# Sch_v1.net
KiCad netlist of a schematic drawn in Altium Designer
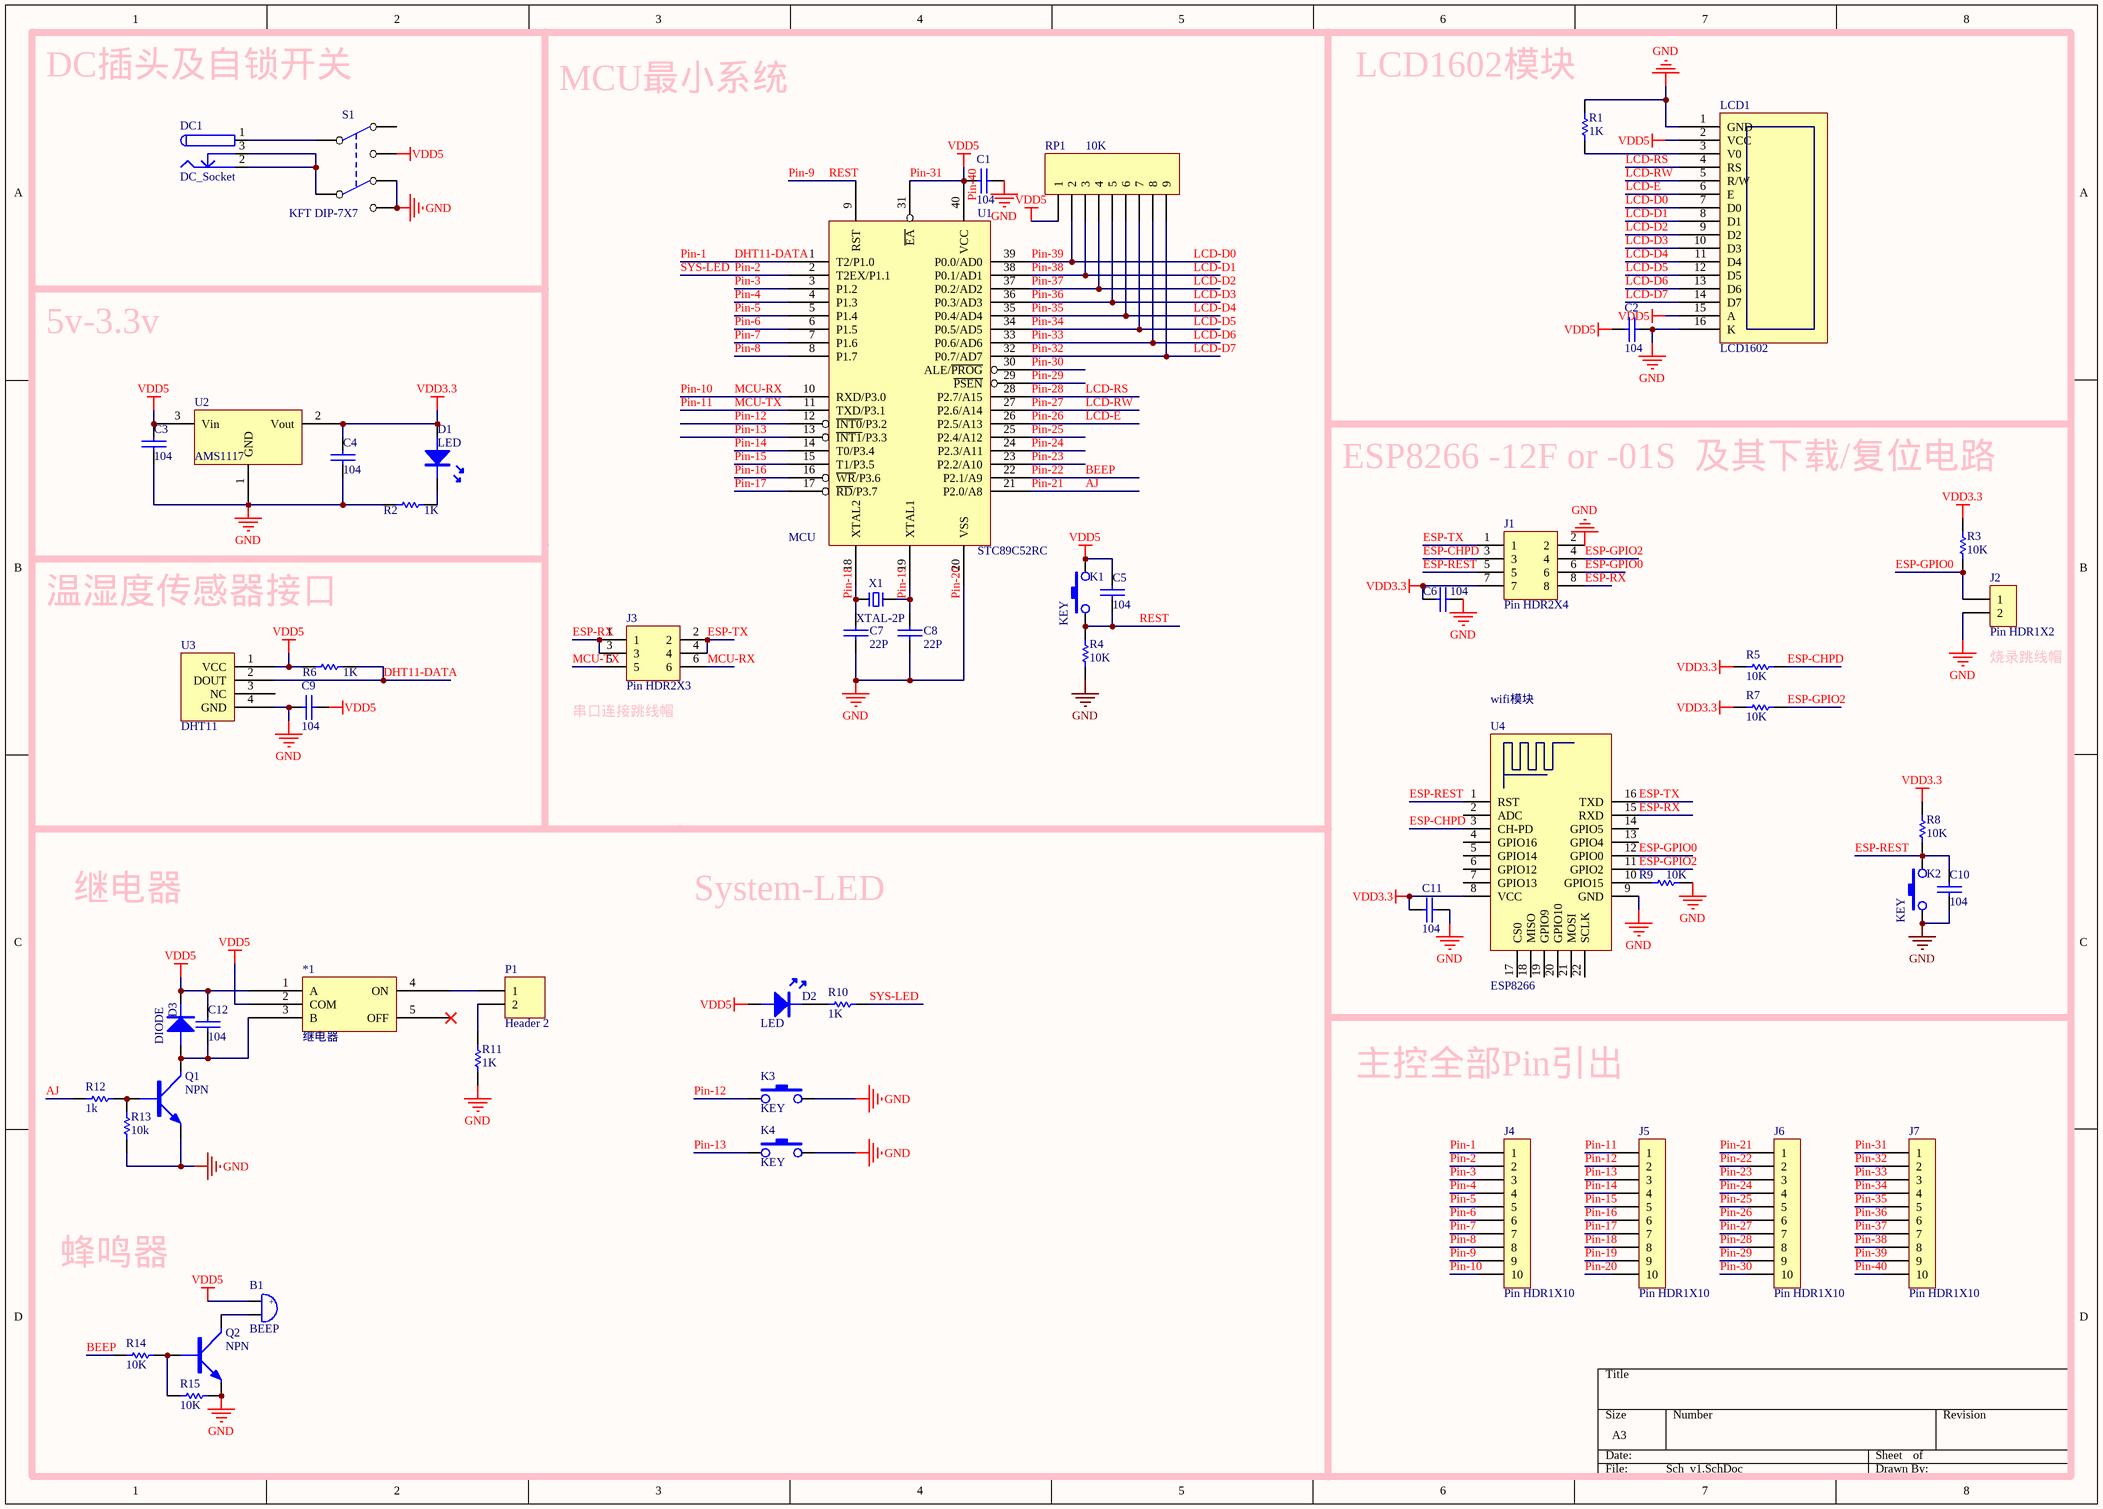
[diagram p0: Sch_v1.SchDoc]

(export (version "E")
  (design (tool "Eeschema 10.0.6"))
  (components
    (comp (ref "*1") (value "继电器") (footprint "继电器") (libsource (lib "test") (part "继电器")))
    (comp (ref "B1")
      (value "BEEP")
      (footprint "BEEP 6.5x12x8.5")
      (description "蜂鸣器")
      (libsource (lib "蜂鸣器") (part "BEEP"))
    )
    (comp (ref "C1")
      (value "104")
      (footprint "0805C")
      (description "无极性电容")
      (libsource (lib "电容") (part "CAP"))
    )
    (comp (ref "C2")
      (value "104")
      (footprint "0805C")
      (description "无极性电容")
      (libsource (lib "电容") (part "CAP"))
    )
    (comp (ref "C3")
      (value "104")
      (footprint "0805C")
      (description "无极性电容")
      (libsource (lib "电容") (part "CAP"))
    )
    (comp (ref "C4")
      (value "104")
      (footprint "0805C")
      (description "无极性电容")
      (libsource (lib "电容") (part "CAP"))
    )
    (comp (ref "C5")
      (value "104")
      (footprint "0805C")
      (description "无极性电容")
      (libsource (lib "电容") (part "CAP"))
    )
    (comp (ref "C6")
      (value "104")
      (footprint "0805C")
      (description "无极性电容")
      (libsource (lib "电容") (part "CAP"))
    )
    (comp (ref "C7")
      (value "22P")
      (footprint "0805C")
      (description "无极性电容")
      (libsource (lib "电容") (part "CAP"))
    )
    (comp (ref "C8")
      (value "22P")
      (footprint "0805C")
      (description "无极性电容")
      (libsource (lib "电容") (part "CAP"))
    )
    (comp (ref "C9")
      (value "104")
      (footprint "0805C")
      (description "无极性电容")
      (libsource (lib "电容") (part "CAP"))
    )
    (comp (ref "C10")
      (value "104")
      (footprint "0805C")
      (description "无极性电容")
      (libsource (lib "电容") (part "CAP"))
    )
    (comp (ref "C11")
      (value "104")
      (footprint "0805C")
      (description "无极性电容")
      (libsource (lib "电容") (part "CAP"))
    )
    (comp (ref "C12")
      (value "104")
      (footprint "0805C")
      (description "无极性电容")
      (libsource (lib "电容") (part "CAP"))
    )
    (comp (ref "D1") (value "LED") (footprint "LED-0805R") (libsource (lib "LED") (part "LED")))
    (comp (ref "D2") (value "LED") (footprint "LED-0805R") (libsource (lib "LED") (part "LED")))
    (comp (ref "D3")
      (value "DIODE")
      (footprint "LL34")
      (description "普通二极管")
      (libsource (lib "二极管") (part "DIODE"))
    )
    (comp (ref "DC1") (value "DC_Socket") (footprint "DC-005") (libsource (lib "电源插座") (part "DC_Socket")))
    (comp (ref "J1")
      (value "Pin HDR2X4")
      (footprint "Pin HDR2X4/2.54mm-S")
      (libsource (lib "排针") (part "Pin HDR2X4"))
    )
    (comp (ref "J2")
      (value "Pin HDR1X2")
      (footprint "Pin HDR1X2/2.54mm-S")
      (libsource (lib "排针") (part "Pin HDR1X2"))
    )
    (comp (ref "J3")
      (value "Pin HDR2X3")
      (footprint "Pin HDR2X3/2.54mm-S")
      (libsource (lib "排针") (part "Pin HDR2X3"))
    )
    (comp (ref "J4")
      (value "Pin HDR1X10")
      (footprint "Pin HDR1X10/2.54mm-S")
      (libsource (lib "排针") (part "Pin HDR1X10"))
    )
    (comp (ref "J5")
      (value "Pin HDR1X10")
      (footprint "Pin HDR1X10/2.54mm-S")
      (libsource (lib "排针") (part "Pin HDR1X10"))
    )
    (comp (ref "J6")
      (value "Pin HDR1X10")
      (footprint "Pin HDR1X10/2.54mm-S")
      (libsource (lib "排针") (part "Pin HDR1X10"))
    )
    (comp (ref "J7")
      (value "Pin HDR1X10")
      (footprint "Pin HDR1X10/2.54mm-S")
      (libsource (lib "排针") (part "Pin HDR1X10"))
    )
    (comp (ref "K1") (value "KEY") (footprint "SMD-3X6X2.5") (libsource (lib "轻触开关") (part "KEY")))
    (comp (ref "K2") (value "KEY") (footprint "SMD-3X6X2.5") (libsource (lib "轻触开关") (part "KEY")))
    (comp (ref "K3") (value "KEY") (footprint "SMD-3X6X2.5") (libsource (lib "轻触开关") (part "KEY")))
    (comp (ref "K4") (value "KEY") (footprint "SMD-3X6X2.5") (libsource (lib "轻触开关") (part "KEY")))
    (comp (ref "LCD1")
      (value "LCD1602")
      (footprint "Fe-HDR1X16/2.54-S")
      (libsource (lib "SS") (part "LCD1602"))
    )
    (comp (ref "P1")
      (value "Header 2")
      (footprint "HDR1X2")
      (description "Header, 2-Pin")
      (fields (field (name "PUBLISHER") "Altium Limited"))
      (libsource (lib "Miscellaneous Connectors") (part "Header 2"))
    )
    (comp (ref "Q1")
      (value "NPN")
      (footprint "SOT-23")
      (description "NPN三极管")
      (libsource (lib "三极管") (part "NPN"))
    )
    (comp (ref "Q2")
      (value "NPN")
      (footprint "SOT-23")
      (description "NPN三极管")
      (libsource (lib "三极管") (part "NPN"))
    )
    (comp (ref "R1") (value "1K") (footprint "0805R") (libsource (lib "电阻") (part "RES")))
    (comp (ref "R2") (value "1K") (footprint "0805R") (libsource (lib "电阻") (part "RES")))
    (comp (ref "R3") (value "10K") (footprint "0805R") (libsource (lib "电阻") (part "RES")))
    (comp (ref "R4") (value "10K") (footprint "0805R") (libsource (lib "电阻") (part "RES")))
    (comp (ref "R5") (value "10K") (footprint "0805R") (libsource (lib "电阻") (part "RES")))
    (comp (ref "R6") (value "1K") (footprint "0805R") (libsource (lib "电阻") (part "RES")))
    (comp (ref "R7") (value "10K") (footprint "0805R") (libsource (lib "电阻") (part "RES")))
    (comp (ref "R8") (value "10K") (footprint "0805R") (libsource (lib "电阻") (part "RES")))
    (comp (ref "R9") (value "10K") (footprint "0805R") (libsource (lib "电阻") (part "RES")))
    (comp (ref "R10") (value "1K") (footprint "0805R") (libsource (lib "电阻") (part "RES")))
    (comp (ref "R11") (value "1K") (footprint "0805R") (libsource (lib "电阻") (part "RES")))
    (comp (ref "R12") (value "1k") (footprint "0805R") (libsource (lib "电阻") (part "RES")))
    (comp (ref "R13") (value "10k") (footprint "0805R") (libsource (lib "电阻") (part "RES")))
    (comp (ref "R14") (value "10K") (footprint "0805R") (libsource (lib "电阻") (part "RES")))
    (comp (ref "R15") (value "10K") (footprint "0805R") (libsource (lib "电阻") (part "RES")))
    (comp (ref "RP1")
      (value "10K")
      (footprint "HDR1X9")
      (description "Header, 9-Pin")
      (fields (field (name "PUBLISHER") "Altium Limited"))
      (libsource (lib "Miscellaneous Connectors") (part "Header 9"))
    )
    (comp (ref "S1")
      (value "KFT DIP-7X7")
      (footprint "KFT DIP-8X8")
      (libsource (lib "电源开关") (part "KFT DIP-7X7"))
    )
    (comp (ref "U1") (value "STC89C52RC") (footprint "DIP40") (libsource (lib "SS") (part "STC89C52RC")))
    (comp (ref "U2")
      (value "AMS1117")
      (footprint "SOT223")
      (description "三端稳压芯片")
      (libsource (lib "电源芯片") (part "AMS1117"))
    )
    (comp (ref "U3") (value "DHT11") (footprint "Fe-HDR1X4/2.54-S") (libsource (lib "SS") (part "DHT11")))
    (comp (ref "U4")
      (value "ESP8266")
      (footprint "WIFIM-SMD_ESP-12F-ESP8266MOD")
      (libsource (lib "Sch_v1") (part "ESP8266"))
    )
    (comp (ref "X1")
      (value "XTAL-2P")
      (footprint "OSC HC-49S")
      (description "2脚无源脚晶振")
      (libsource (lib "晶振") (part "XTAL-2P"))
    )
  )
  (nets
    (net (code "1") (name "/AJ") (class "Default")
      (node (ref "J6") (pin "1") (pinfunction "1_1") (pintype "passive"))
      (node (ref "R12") (pin "2") (pinfunction "2_2") (pintype "passive"))
      (node (ref "U1") (pin "21") (pinfunction "P2.0/A8_21") (pintype "passive"))
    )
    (net (code "2") (name "/BEEP") (class "Default")
      (node (ref "J6") (pin "2") (pinfunction "2_2") (pintype "passive"))
      (node (ref "R14") (pin "2") (pinfunction "2_2") (pintype "passive"))
      (node (ref "U1") (pin "22") (pinfunction "P2.1/A9_22") (pintype "passive"))
    )
    (net (code "3") (name "/DHT11-DATA") (class "Default")
      (node (ref "J4") (pin "1") (pinfunction "1_1") (pintype "passive"))
      (node (ref "R6") (pin "1") (pinfunction "1_1") (pintype "passive"))
      (node (ref "U1") (pin "1") (pinfunction "T2/P1.0_1") (pintype "passive"))
      (node (ref "U3") (pin "2") (pinfunction "DOUT_2") (pintype "passive"))
    )
    (net (code "4") (name "/ESP-CHPD") (class "Default")
      (node (ref "J1") (pin "3") (pinfunction "3_3") (pintype "passive"))
      (node (ref "R5") (pin "2") (pinfunction "2_2") (pintype "passive"))
      (node (ref "U4") (pin "3") (pinfunction "CH-PD_3") (pintype "passive"))
    )
    (net (code "5") (name "/ESP-GPIO0") (class "Default")
      (node (ref "J1") (pin "6") (pinfunction "6_6") (pintype "passive"))
      (node (ref "J2") (pin "1") (pinfunction "1_1") (pintype "passive"))
      (node (ref "R3") (pin "1") (pinfunction "1_1") (pintype "passive"))
      (node (ref "U4") (pin "12") (pinfunction "GPIO0_12") (pintype "passive"))
    )
    (net (code "6") (name "/ESP-GPIO2") (class "Default")
      (node (ref "J1") (pin "4") (pinfunction "4_4") (pintype "passive"))
      (node (ref "R7") (pin "2") (pinfunction "2_2") (pintype "passive"))
      (node (ref "U4") (pin "11") (pinfunction "GPIO2_11") (pintype "passive"))
    )
    (net (code "7") (name "/ESP-REST") (class "Default")
      (node (ref "C10") (pin "2") (pinfunction "2_2") (pintype "passive"))
      (node (ref "J1") (pin "5") (pinfunction "5_5") (pintype "passive"))
      (node (ref "K2") (pin "3") (pinfunction "3_3") (pintype "passive"))
      (node (ref "R8") (pin "1") (pinfunction "1_1") (pintype "passive"))
      (node (ref "U4") (pin "1") (pinfunction "RST_1") (pintype "open_emitter"))
    )
    (net (code "8") (name "/ESP-RX") (class "Default")
      (node (ref "J1") (pin "8") (pinfunction "8_8") (pintype "passive"))
      (node (ref "J3") (pin "1") (pinfunction "1_1") (pintype "passive"))
      (node (ref "J3") (pin "3") (pinfunction "3_3") (pintype "passive"))
      (node (ref "U4") (pin "15") (pinfunction "RXD_15") (pintype "passive"))
    )
    (net (code "9") (name "/ESP-TX") (class "Default")
      (node (ref "J1") (pin "1") (pinfunction "1_1") (pintype "passive"))
      (node (ref "J3") (pin "2") (pinfunction "2_2") (pintype "passive"))
      (node (ref "J3") (pin "4") (pinfunction "4_4") (pintype "passive"))
      (node (ref "U4") (pin "16") (pinfunction "TXD_16") (pintype "passive"))
    )
    (net (code "10") (name "/LCD-D0") (class "Default")
      (node (ref "J7") (pin "9") (pinfunction "9_9") (pintype "passive"))
      (node (ref "LCD1") (pin "7") (pinfunction "D0_7") (pintype "passive"))
      (node (ref "RP1") (pin "2") (pinfunction "2_2") (pintype "passive"))
      (node (ref "U1") (pin "39") (pinfunction "P0.0/AD0_39") (pintype "passive"))
    )
    (net (code "11") (name "/LCD-D1") (class "Default")
      (node (ref "J7") (pin "8") (pinfunction "8_8") (pintype "passive"))
      (node (ref "LCD1") (pin "8") (pinfunction "D1_8") (pintype "passive"))
      (node (ref "RP1") (pin "3") (pinfunction "3_3") (pintype "passive"))
      (node (ref "U1") (pin "38") (pinfunction "P0.1/AD1_38") (pintype "passive"))
    )
    (net (code "12") (name "/LCD-D2") (class "Default")
      (node (ref "J7") (pin "7") (pinfunction "7_7") (pintype "passive"))
      (node (ref "LCD1") (pin "9") (pinfunction "D2_9") (pintype "passive"))
      (node (ref "RP1") (pin "4") (pinfunction "4_4") (pintype "passive"))
      (node (ref "U1") (pin "37") (pinfunction "P0.2/AD2_37") (pintype "passive"))
    )
    (net (code "13") (name "/LCD-D3") (class "Default")
      (node (ref "J7") (pin "6") (pinfunction "6_6") (pintype "passive"))
      (node (ref "LCD1") (pin "10") (pinfunction "D3_10") (pintype "passive"))
      (node (ref "RP1") (pin "5") (pinfunction "5_5") (pintype "passive"))
      (node (ref "U1") (pin "36") (pinfunction "P0.3/AD3_36") (pintype "passive"))
    )
    (net (code "14") (name "/LCD-D4") (class "Default")
      (node (ref "J7") (pin "5") (pinfunction "5_5") (pintype "passive"))
      (node (ref "LCD1") (pin "11") (pinfunction "D4_11") (pintype "passive"))
      (node (ref "RP1") (pin "6") (pinfunction "6_6") (pintype "passive"))
      (node (ref "U1") (pin "35") (pinfunction "P0.4/AD4_35") (pintype "passive"))
    )
    (net (code "15") (name "/LCD-D5") (class "Default")
      (node (ref "J7") (pin "4") (pinfunction "4_4") (pintype "passive"))
      (node (ref "LCD1") (pin "12") (pinfunction "D5_12") (pintype "passive"))
      (node (ref "RP1") (pin "7") (pinfunction "7_7") (pintype "passive"))
      (node (ref "U1") (pin "34") (pinfunction "P0.5/AD5_34") (pintype "passive"))
    )
    (net (code "16") (name "/LCD-D6") (class "Default")
      (node (ref "J7") (pin "3") (pinfunction "3_3") (pintype "passive"))
      (node (ref "LCD1") (pin "13") (pinfunction "D6_13") (pintype "passive"))
      (node (ref "RP1") (pin "8") (pinfunction "8_8") (pintype "passive"))
      (node (ref "U1") (pin "33") (pinfunction "P0.6/AD6_33") (pintype "passive"))
    )
    (net (code "17") (name "/LCD-D7") (class "Default")
      (node (ref "J7") (pin "2") (pinfunction "2_2") (pintype "passive"))
      (node (ref "LCD1") (pin "14") (pinfunction "D7_14") (pintype "passive"))
      (node (ref "RP1") (pin "9") (pinfunction "9_9") (pintype "passive"))
      (node (ref "U1") (pin "32") (pinfunction "P0.7/AD7_32") (pintype "passive"))
    )
    (net (code "18") (name "/LCD-E") (class "Default")
      (node (ref "J6") (pin "6") (pinfunction "6_6") (pintype "passive"))
      (node (ref "LCD1") (pin "6") (pinfunction "E_6") (pintype "passive"))
      (node (ref "U1") (pin "26") (pinfunction "P2.5/A13_26") (pintype "passive"))
    )
    (net (code "19") (name "/LCD-RS") (class "Default")
      (node (ref "J6") (pin "8") (pinfunction "8_8") (pintype "passive"))
      (node (ref "LCD1") (pin "4") (pinfunction "RS_4") (pintype "passive"))
      (node (ref "U1") (pin "28") (pinfunction "P2.7/A15_28") (pintype "passive"))
    )
    (net (code "20") (name "/LCD-RW") (class "Default")
      (node (ref "J6") (pin "7") (pinfunction "7_7") (pintype "passive"))
      (node (ref "LCD1") (pin "5") (pinfunction "R/W_5") (pintype "passive"))
      (node (ref "U1") (pin "27") (pinfunction "P2.6/A14_27") (pintype "passive"))
    )
    (net (code "21") (name "/MCU-RX") (class "Default")
      (node (ref "J3") (pin "6") (pinfunction "6_6") (pintype "passive"))
      (node (ref "J4") (pin "10") (pinfunction "10_10") (pintype "passive"))
      (node (ref "U1") (pin "10") (pinfunction "RXD/P3.0_10") (pintype "passive"))
    )
    (net (code "22") (name "/MCU-TX") (class "Default")
      (node (ref "J3") (pin "5") (pinfunction "5_5") (pintype "passive"))
      (node (ref "J5") (pin "1") (pinfunction "1_1") (pintype "passive"))
      (node (ref "U1") (pin "11") (pinfunction "TXD/P3.1_11") (pintype "passive"))
    )
    (net (code "23") (name "/Pin-2") (class "Default")
      (node (ref "J4") (pin "2") (pinfunction "2_2") (pintype "passive"))
      (node (ref "R10") (pin "2") (pinfunction "2_2") (pintype "passive"))
      (node (ref "U1") (pin "2") (pinfunction "T2EX/P1.1_2") (pintype "passive"))
    )
    (net (code "24") (name "/Pin-3") (class "Default")
      (node (ref "J4") (pin "3") (pinfunction "3_3") (pintype "passive"))
      (node (ref "U1") (pin "3") (pinfunction "P1.2_3") (pintype "passive"))
    )
    (net (code "25") (name "/Pin-4") (class "Default")
      (node (ref "J4") (pin "4") (pinfunction "4_4") (pintype "passive"))
      (node (ref "U1") (pin "4") (pinfunction "P1.3_4") (pintype "passive"))
    )
    (net (code "26") (name "/Pin-5") (class "Default")
      (node (ref "J4") (pin "5") (pinfunction "5_5") (pintype "passive"))
      (node (ref "U1") (pin "5") (pinfunction "P1.4_5") (pintype "passive"))
    )
    (net (code "27") (name "/Pin-6") (class "Default")
      (node (ref "J4") (pin "6") (pinfunction "6_6") (pintype "passive"))
      (node (ref "U1") (pin "6") (pinfunction "P1.5_6") (pintype "passive"))
    )
    (net (code "28") (name "/Pin-7") (class "Default")
      (node (ref "J4") (pin "7") (pinfunction "7_7") (pintype "passive"))
      (node (ref "U1") (pin "7") (pinfunction "P1.6_7") (pintype "passive"))
    )
    (net (code "29") (name "/Pin-8") (class "Default")
      (node (ref "J4") (pin "8") (pinfunction "8_8") (pintype "passive"))
      (node (ref "U1") (pin "8") (pinfunction "P1.7_8") (pintype "passive"))
    )
    (net (code "30") (name "/Pin-9") (class "Default")
      (node (ref "C5") (pin "1") (pinfunction "1_1") (pintype "passive"))
      (node (ref "J4") (pin "9") (pinfunction "9_9") (pintype "passive"))
      (node (ref "K1") (pin "1") (pinfunction "1_1") (pintype "passive"))
      (node (ref "R4") (pin "2") (pinfunction "2_2") (pintype "passive"))
      (node (ref "U1") (pin "9") (pinfunction "RST_9") (pintype "passive"))
    )
    (net (code "31") (name "/Pin-12") (class "Default")
      (node (ref "J5") (pin "2") (pinfunction "2_2") (pintype "passive"))
      (node (ref "K3") (pin "1") (pinfunction "1_1") (pintype "passive"))
      (node (ref "U1") (pin "12") (pinfunction "~{INT0}/P3.2_12") (pintype "passive"))
    )
    (net (code "32") (name "/Pin-13") (class "Default")
      (node (ref "J5") (pin "3") (pinfunction "3_3") (pintype "passive"))
      (node (ref "K4") (pin "1") (pinfunction "1_1") (pintype "passive"))
      (node (ref "U1") (pin "13") (pinfunction "~{INT1}/P3.3_13") (pintype "passive"))
    )
    (net (code "33") (name "/Pin-14") (class "Default")
      (node (ref "J5") (pin "4") (pinfunction "4_4") (pintype "passive"))
      (node (ref "U1") (pin "14") (pinfunction "T0/P3.4_14") (pintype "passive"))
    )
    (net (code "34") (name "/Pin-15") (class "Default")
      (node (ref "J5") (pin "5") (pinfunction "5_5") (pintype "passive"))
      (node (ref "U1") (pin "15") (pinfunction "T1/P3.5_15") (pintype "passive"))
    )
    (net (code "35") (name "/Pin-16") (class "Default")
      (node (ref "J5") (pin "6") (pinfunction "6_6") (pintype "passive"))
      (node (ref "U1") (pin "16") (pinfunction "~{WR}/P3.6_16") (pintype "passive"))
    )
    (net (code "36") (name "/Pin-17") (class "Default")
      (node (ref "J5") (pin "7") (pinfunction "7_7") (pintype "passive"))
      (node (ref "U1") (pin "17") (pinfunction "~{RD}/P3.7_17") (pintype "passive"))
    )
    (net (code "37") (name "/Pin-18") (class "Default")
      (node (ref "C7") (pin "2") (pinfunction "2_2") (pintype "passive"))
      (node (ref "J5") (pin "8") (pinfunction "8_8") (pintype "passive"))
      (node (ref "U1") (pin "18") (pinfunction "XTAL2_18") (pintype "passive"))
      (node (ref "X1") (pin "1") (pinfunction "1_1") (pintype "passive"))
    )
    (net (code "38") (name "/Pin-19") (class "Default")
      (node (ref "C8") (pin "2") (pinfunction "2_2") (pintype "passive"))
      (node (ref "J5") (pin "9") (pinfunction "9_9") (pintype "passive"))
      (node (ref "U1") (pin "19") (pinfunction "XTAL1_19") (pintype "passive"))
      (node (ref "X1") (pin "2") (pinfunction "2_2") (pintype "passive"))
    )
    (net (code "39") (name "/Pin-23") (class "Default")
      (node (ref "J6") (pin "3") (pinfunction "3_3") (pintype "passive"))
      (node (ref "U1") (pin "23") (pinfunction "P2.2/A10_23") (pintype "passive"))
    )
    (net (code "40") (name "/Pin-24") (class "Default")
      (node (ref "J6") (pin "4") (pinfunction "4_4") (pintype "passive"))
      (node (ref "U1") (pin "24") (pinfunction "P2.3/A11_24") (pintype "passive"))
    )
    (net (code "41") (name "/Pin-25") (class "Default")
      (node (ref "J6") (pin "5") (pinfunction "5_5") (pintype "passive"))
      (node (ref "U1") (pin "25") (pinfunction "P2.4/A12_25") (pintype "passive"))
    )
    (net (code "42") (name "/Pin-29") (class "Default")
      (node (ref "J6") (pin "9") (pinfunction "9_9") (pintype "passive"))
      (node (ref "U1") (pin "29") (pinfunction "~{PSEN}_29") (pintype "passive"))
    )
    (net (code "43") (name "/Pin-30") (class "Default")
      (node (ref "J6") (pin "10") (pinfunction "10_10") (pintype "passive"))
      (node (ref "U1") (pin "30") (pinfunction "ALE/~{PROG}_30") (pintype "passive"))
    )
    (net (code "44") (name "GND") (class "Default")
      (node (ref "C1") (pin "1") (pinfunction "1_1") (pintype "passive"))
      (node (ref "C10") (pin "1") (pinfunction "1_1") (pintype "passive"))
      (node (ref "C11") (pin "1") (pinfunction "1_1") (pintype "passive"))
      (node (ref "C2") (pin "1") (pinfunction "1_1") (pintype "passive"))
      (node (ref "C3") (pin "1") (pinfunction "1_1") (pintype "passive"))
      (node (ref "C4") (pin "1") (pinfunction "1_1") (pintype "passive"))
      (node (ref "C6") (pin "1") (pinfunction "1_1") (pintype "passive"))
      (node (ref "C7") (pin "1") (pinfunction "1_1") (pintype "passive"))
      (node (ref "C8") (pin "1") (pinfunction "1_1") (pintype "passive"))
      (node (ref "C9") (pin "2") (pinfunction "2_2") (pintype "passive"))
      (node (ref "J1") (pin "2") (pinfunction "2_2") (pintype "passive"))
      (node (ref "J2") (pin "2") (pinfunction "2_2") (pintype "passive"))
      (node (ref "J5") (pin "10") (pinfunction "10_10") (pintype "passive"))
      (node (ref "K2") (pin "1") (pinfunction "1_1") (pintype "passive"))
      (node (ref "K3") (pin "3") (pinfunction "3_3") (pintype "passive"))
      (node (ref "K4") (pin "3") (pinfunction "3_3") (pintype "passive"))
      (node (ref "LCD1") (pin "1") (pinfunction "GND_1") (pintype "passive"))
      (node (ref "LCD1") (pin "16") (pinfunction "K_16") (pintype "passive"))
      (node (ref "Q1") (pin "E") (pinfunction "E_E") (pintype "passive"))
      (node (ref "Q2") (pin "E") (pinfunction "E_E") (pintype "passive"))
      (node (ref "R1") (pin "1") (pinfunction "1_1") (pintype "passive"))
      (node (ref "R11") (pin "2") (pinfunction "2_2") (pintype "passive"))
      (node (ref "R13") (pin "1") (pinfunction "1_1") (pintype "passive"))
      (node (ref "R15") (pin "1") (pinfunction "1_1") (pintype "passive"))
      (node (ref "R2") (pin "2") (pinfunction "2_2") (pintype "passive"))
      (node (ref "R4") (pin "1") (pinfunction "1_1") (pintype "passive"))
      (node (ref "R9") (pin "1") (pinfunction "1_1") (pintype "passive"))
      (node (ref "S1") (pin "4") (pinfunction "4_4") (pintype "passive"))
      (node (ref "S1") (pin "6") (pinfunction "6_6") (pintype "passive"))
      (node (ref "U1") (pin "20") (pinfunction "VSS_20") (pintype "passive"))
      (node (ref "U2") (pin "1") (pinfunction "GND_1") (pintype "passive"))
      (node (ref "U3") (pin "4") (pinfunction "GND_4") (pintype "passive"))
      (node (ref "U4") (pin "9") (pinfunction "GND_9") (pintype "passive"))
    )
    (net (code "45") (name "Net-(*1-B)") (class "Default")
      (node (ref "*1") (pin "3") (pinfunction "B_3") (pintype "passive"))
      (node (ref "C12") (pin "1") (pinfunction "1_1") (pintype "passive"))
      (node (ref "D3") (pin "A") (pinfunction "A_A") (pintype "passive"))
      (node (ref "Q1") (pin "C") (pinfunction "C_C") (pintype "passive"))
    )
    (net (code "46") (name "Net-(*1-ON)") (class "Default")
      (node (ref "*1") (pin "4") (pinfunction "ON_4") (pintype "passive"))
      (node (ref "P1") (pin "1") (pinfunction "1_1") (pintype "passive"))
    )
    (net (code "47") (name "Net-(B1-Pad2)") (class "Default")
      (node (ref "B1") (pin "2") (pinfunction "2_2") (pintype "passive"))
      (node (ref "Q2") (pin "C") (pinfunction "C_C") (pintype "passive"))
    )
    (net (code "48") (name "Net-(D1-PadK)") (class "Default")
      (node (ref "D1") (pin "K") (pinfunction "K_K") (pintype "passive"))
      (node (ref "R2") (pin "1") (pinfunction "1_1") (pintype "passive"))
    )
    (net (code "49") (name "Net-(D2-PadK)") (class "Default")
      (node (ref "D2") (pin "K") (pinfunction "K_K") (pintype "passive"))
      (node (ref "R10") (pin "1") (pinfunction "1_1") (pintype "passive"))
    )
    (net (code "50") (name "Net-(DC1-Pad1)") (class "Default")
      (node (ref "DC1") (pin "1") (pinfunction "1_1") (pintype "power_in"))
      (node (ref "S1") (pin "2") (pinfunction "2_2") (pintype "passive"))
    )
    (net (code "51") (name "Net-(DC1-Pad2)") (class "Default")
      (node (ref "DC1") (pin "2") (pinfunction "2_2") (pintype "power_in"))
      (node (ref "DC1") (pin "3") (pinfunction "3_3") (pintype "power_in"))
      (node (ref "S1") (pin "5") (pinfunction "5_5") (pintype "passive"))
    )
    (net (code "52") (name "Net-(LCD1-V0)") (class "Default")
      (node (ref "LCD1") (pin "3") (pinfunction "V0_3") (pintype "passive"))
      (node (ref "R1") (pin "2") (pinfunction "2_2") (pintype "passive"))
    )
    (net (code "53") (name "Net-(P1-Pad2)") (class "Default")
      (node (ref "P1") (pin "2") (pinfunction "2_2") (pintype "passive"))
      (node (ref "R11") (pin "1") (pinfunction "1_1") (pintype "passive"))
    )
    (net (code "54") (name "Net-(Q1-PadB)") (class "Default")
      (node (ref "Q1") (pin "B") (pinfunction "B_B") (pintype "passive"))
      (node (ref "R12") (pin "1") (pinfunction "1_1") (pintype "passive"))
      (node (ref "R13") (pin "2") (pinfunction "2_2") (pintype "passive"))
    )
    (net (code "55") (name "Net-(Q2-PadB)") (class "Default")
      (node (ref "Q2") (pin "B") (pinfunction "B_B") (pintype "passive"))
      (node (ref "R14") (pin "1") (pinfunction "1_1") (pintype "passive"))
      (node (ref "R15") (pin "2") (pinfunction "2_2") (pintype "passive"))
    )
    (net (code "56") (name "Net-(U4-GPIO15)") (class "Default")
      (node (ref "R9") (pin "2") (pinfunction "2_2") (pintype "passive"))
      (node (ref "U4") (pin "10") (pinfunction "GPIO15_10") (pintype "passive"))
    )
    (net (code "57") (name "VDD3.3") (class "Default")
      (node (ref "C11") (pin "2") (pinfunction "2_2") (pintype "passive"))
      (node (ref "C4") (pin "2") (pinfunction "2_2") (pintype "passive"))
      (node (ref "C6") (pin "2") (pinfunction "2_2") (pintype "passive"))
      (node (ref "D1") (pin "A") (pinfunction "A_A") (pintype "passive"))
      (node (ref "J1") (pin "7") (pinfunction "7_7") (pintype "passive"))
      (node (ref "R3") (pin "2") (pinfunction "2_2") (pintype "passive"))
      (node (ref "R5") (pin "1") (pinfunction "1_1") (pintype "passive"))
      (node (ref "R7") (pin "1") (pinfunction "1_1") (pintype "passive"))
      (node (ref "R8") (pin "2") (pinfunction "2_2") (pintype "passive"))
      (node (ref "U2") (pin "2") (pinfunction "Vout_2") (pintype "passive"))
      (node (ref "U4") (pin "8") (pinfunction "VCC_8") (pintype "passive"))
    )
    (net (code "58") (name "VDD5") (class "Default")
      (node (ref "*1") (pin "1") (pinfunction "A_1") (pintype "passive"))
      (node (ref "*1") (pin "2") (pinfunction "COM_2") (pintype "passive"))
      (node (ref "B1") (pin "1") (pinfunction "1_1") (pintype "passive"))
      (node (ref "C1") (pin "2") (pinfunction "2_2") (pintype "passive"))
      (node (ref "C12") (pin "2") (pinfunction "2_2") (pintype "passive"))
      (node (ref "C2") (pin "2") (pinfunction "2_2") (pintype "passive"))
      (node (ref "C3") (pin "2") (pinfunction "2_2") (pintype "passive"))
      (node (ref "C5") (pin "2") (pinfunction "2_2") (pintype "passive"))
      (node (ref "C9") (pin "1") (pinfunction "1_1") (pintype "passive"))
      (node (ref "D2") (pin "A") (pinfunction "A_A") (pintype "passive"))
      (node (ref "D3") (pin "K") (pinfunction "K_K") (pintype "passive"))
      (node (ref "J7") (pin "1") (pinfunction "1_1") (pintype "passive"))
      (node (ref "J7") (pin "10") (pinfunction "10_10") (pintype "passive"))
      (node (ref "K1") (pin "3") (pinfunction "3_3") (pintype "passive"))
      (node (ref "LCD1") (pin "15") (pinfunction "A_15") (pintype "passive"))
      (node (ref "LCD1") (pin "2") (pinfunction "VCC_2") (pintype "passive"))
      (node (ref "R6") (pin "2") (pinfunction "2_2") (pintype "passive"))
      (node (ref "RP1") (pin "1") (pinfunction "1_1") (pintype "passive"))
      (node (ref "S1") (pin "1") (pinfunction "1_1") (pintype "passive"))
      (node (ref "U1") (pin "31") (pinfunction "~{EA}_31") (pintype "passive"))
      (node (ref "U1") (pin "40") (pinfunction "VCC_40") (pintype "passive"))
      (node (ref "U2") (pin "3") (pinfunction "Vin_3") (pintype "passive"))
      (node (ref "U3") (pin "1") (pinfunction "VCC_1") (pintype "passive"))
    )
    (net (code "59") (name "unconnected-(*1-OFF-Pad5)") (class "Default")
      (node (ref "*1") (pin "5") (pinfunction "OFF_5") (pintype "passive+no_connect"))
    )
    (net (code "60") (name "unconnected-(S1-Pad3)") (class "Default")
      (node (ref "S1") (pin "3") (pinfunction "3_3") (pintype "passive"))
    )
    (net (code "61") (name "unconnected-(U3-NC-Pad3)") (class "Default")
      (node (ref "U3") (pin "3") (pinfunction "NC_3") (pintype "passive"))
    )
    (net (code "62") (name "unconnected-(U4-ADC-Pad2)") (class "Default")
      (node (ref "U4") (pin "2") (pinfunction "ADC_2") (pintype "passive"))
    )
    (net (code "63") (name "unconnected-(U4-CS0-Pad17)") (class "Default")
      (node (ref "U4") (pin "17") (pinfunction "CS0_17") (pintype "passive"))
    )
    (net (code "64") (name "unconnected-(U4-GPIO4-Pad13)") (class "Default")
      (node (ref "U4") (pin "13") (pinfunction "GPIO4_13") (pintype "passive"))
    )
    (net (code "65") (name "unconnected-(U4-GPIO5-Pad14)") (class "Default")
      (node (ref "U4") (pin "14") (pinfunction "GPIO5_14") (pintype "passive"))
    )
    (net (code "66") (name "unconnected-(U4-GPIO9-Pad19)") (class "Default")
      (node (ref "U4") (pin "19") (pinfunction "GPIO9_19") (pintype "passive"))
    )
    (net (code "67") (name "unconnected-(U4-GPIO10-Pad20)") (class "Default")
      (node (ref "U4") (pin "20") (pinfunction "GPIO10_20") (pintype "passive"))
    )
    (net (code "68") (name "unconnected-(U4-GPIO12-Pad6)") (class "Default")
      (node (ref "U4") (pin "6") (pinfunction "GPIO12_6") (pintype "passive"))
    )
    (net (code "69") (name "unconnected-(U4-GPIO13-Pad7)") (class "Default")
      (node (ref "U4") (pin "7") (pinfunction "GPIO13_7") (pintype "passive"))
    )
    (net (code "70") (name "unconnected-(U4-GPIO14-Pad5)") (class "Default")
      (node (ref "U4") (pin "5") (pinfunction "GPIO14_5") (pintype "passive"))
    )
    (net (code "71") (name "unconnected-(U4-GPIO16-Pad4)") (class "Default")
      (node (ref "U4") (pin "4") (pinfunction "GPIO16_4") (pintype "passive"))
    )
    (net (code "72") (name "unconnected-(U4-MISO-Pad18)") (class "Default")
      (node (ref "U4") (pin "18") (pinfunction "MISO_18") (pintype "passive"))
    )
    (net (code "73") (name "unconnected-(U4-MOSI-Pad21)") (class "Default")
      (node (ref "U4") (pin "21") (pinfunction "MOSI_21") (pintype "passive"))
    )
    (net (code "74") (name "unconnected-(U4-SCLK-Pad22)") (class "Default")
      (node (ref "U4") (pin "22") (pinfunction "SCLK_22") (pintype "passive"))
    )
  )
)
